# R-schematic.net
KiCad netlist of a schematic drawn in EAGLE
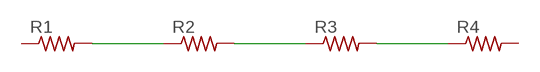
[diagram p0: schematic, sheet 1]

(export (version "E")
  (design (tool "Eeschema 10.0.6"))
  (components
    (comp (ref "R1")
      (value "R-US_M1206")
      (footprint "eagle-import:M1206")
      (libsource (lib "eagle-import") (part "R-US_M1206"))
    )
    (comp (ref "R2")
      (value "R-US_M1206")
      (footprint "eagle-import:M1206")
      (libsource (lib "eagle-import") (part "R-US_M1206"))
    )
    (comp (ref "R3")
      (value "R-US_M1206")
      (footprint "eagle-import:M1206")
      (libsource (lib "eagle-import") (part "R-US_M1206"))
    )
    (comp (ref "R4")
      (value "R-US_M1206")
      (footprint "eagle-import:M1206")
      (libsource (lib "eagle-import") (part "R-US_M1206"))
    )
  )
  (nets
    (net (code "1") (name "Net-(R1-Pad2)") (class "Default")
      (node (ref "R1") (pin "2") (pinfunction "2_2") (pintype "passive"))
      (node (ref "R2") (pin "1") (pinfunction "1_1") (pintype "passive"))
    )
    (net (code "2") (name "Net-(R2-Pad2)") (class "Default")
      (node (ref "R2") (pin "2") (pinfunction "2_2") (pintype "passive"))
      (node (ref "R3") (pin "1") (pinfunction "1_1") (pintype "passive"))
    )
    (net (code "3") (name "Net-(R3-Pad2)") (class "Default")
      (node (ref "R3") (pin "2") (pinfunction "2_2") (pintype "passive"))
      (node (ref "R4") (pin "1") (pinfunction "1_1") (pintype "passive"))
    )
    (net (code "4") (name "unconnected-(R1-Pad1)") (class "Default")
      (node (ref "R1") (pin "1") (pinfunction "1_1") (pintype "passive"))
    )
    (net (code "5") (name "unconnected-(R4-Pad2)") (class "Default")
      (node (ref "R4") (pin "2") (pinfunction "2_2") (pintype "passive"))
    )
  )
)
